# control_board.net
KiCad netlist of a schematic drawn in EAGLE
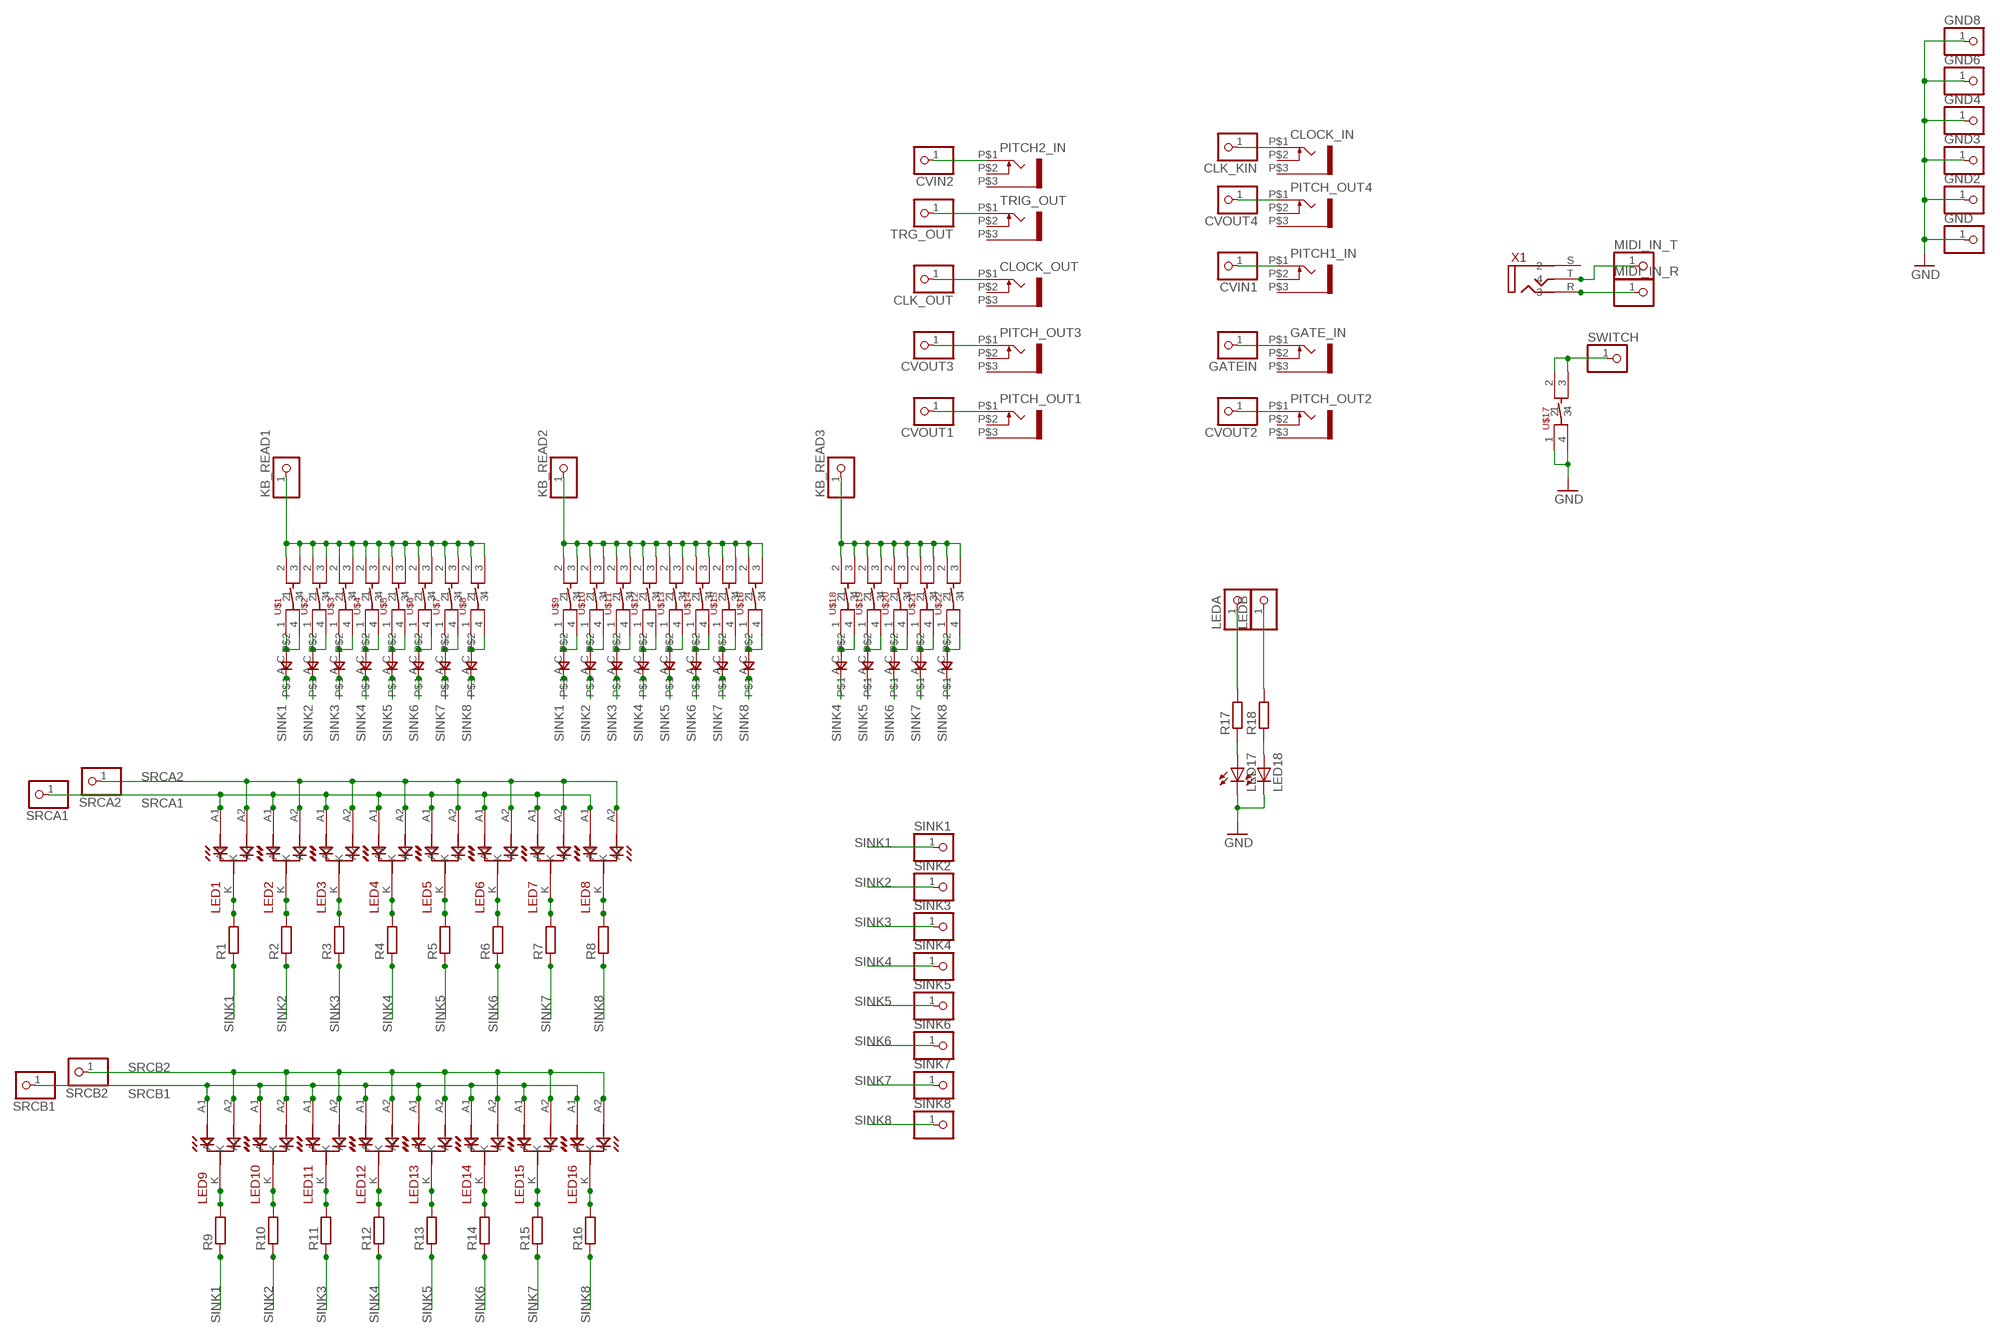
[diagram p0: schematic, sheet 1]

(export (version "E")
  (design (tool "Eeschema 10.0.6"))
  (components
    (comp (ref "CLK_KIN")
      (value "PINHD-1X1")
      (footprint "eagle-import:1X01")
      (libsource (lib "eagle-import") (part "PINHD-1X1"))
    )
    (comp (ref "CLK_OUT")
      (value "PINHD-1X1")
      (footprint "eagle-import:1X01")
      (libsource (lib "eagle-import") (part "PINHD-1X1"))
    )
    (comp (ref "CLOCK_IN")
      (value "WQP-PJ301M-12_JACK")
      (footprint "eagle-import:WQP-PJ301M-12_JACK")
      (libsource (lib "eagle-import") (part "WQP-PJ301M-12_JACK"))
    )
    (comp (ref "CLOCK_OUT")
      (value "WQP-PJ301M-12_JACK")
      (footprint "eagle-import:WQP-PJ301M-12_JACK")
      (libsource (lib "eagle-import") (part "WQP-PJ301M-12_JACK"))
    )
    (comp (ref "CVIN1")
      (value "PINHD-1X1")
      (footprint "eagle-import:1X01")
      (libsource (lib "eagle-import") (part "PINHD-1X1"))
    )
    (comp (ref "CVIN2")
      (value "PINHD-1X1")
      (footprint "eagle-import:1X01")
      (libsource (lib "eagle-import") (part "PINHD-1X1"))
    )
    (comp (ref "CVOUT1")
      (value "PINHD-1X1")
      (footprint "eagle-import:1X01")
      (libsource (lib "eagle-import") (part "PINHD-1X1"))
    )
    (comp (ref "CVOUT2")
      (value "PINHD-1X1")
      (footprint "eagle-import:1X01")
      (libsource (lib "eagle-import") (part "PINHD-1X1"))
    )
    (comp (ref "CVOUT3")
      (value "PINHD-1X1")
      (footprint "eagle-import:1X01")
      (libsource (lib "eagle-import") (part "PINHD-1X1"))
    )
    (comp (ref "CVOUT4")
      (value "PINHD-1X1")
      (footprint "eagle-import:1X01")
      (libsource (lib "eagle-import") (part "PINHD-1X1"))
    )
    (comp (ref "GATEIN")
      (value "PINHD-1X1")
      (footprint "eagle-import:1X01")
      (libsource (lib "eagle-import") (part "PINHD-1X1"))
    )
    (comp (ref "GATE_IN")
      (value "WQP-PJ301M-12_JACK")
      (footprint "eagle-import:WQP-PJ301M-12_JACK")
      (libsource (lib "eagle-import") (part "WQP-PJ301M-12_JACK"))
    )
    (comp (ref "GND")
      (value "PINHD-1X1")
      (footprint "eagle-import:1X01")
      (libsource (lib "eagle-import") (part "PINHD-1X1"))
    )
    (comp (ref "GND2")
      (value "PINHD-1X1")
      (footprint "eagle-import:1X01")
      (libsource (lib "eagle-import") (part "PINHD-1X1"))
    )
    (comp (ref "GND3")
      (value "PINHD-1X1")
      (footprint "eagle-import:1X01")
      (libsource (lib "eagle-import") (part "PINHD-1X1"))
    )
    (comp (ref "GND4")
      (value "PINHD-1X1")
      (footprint "eagle-import:1X01")
      (libsource (lib "eagle-import") (part "PINHD-1X1"))
    )
    (comp (ref "GND6")
      (value "PINHD-1X1")
      (footprint "eagle-import:1X01")
      (libsource (lib "eagle-import") (part "PINHD-1X1"))
    )
    (comp (ref "GND8")
      (value "PINHD-1X1")
      (footprint "eagle-import:1X01")
      (libsource (lib "eagle-import") (part "PINHD-1X1"))
    )
    (comp (ref "KB_READ1")
      (value "PINHD-1X1")
      (footprint "eagle-import:1X01")
      (libsource (lib "eagle-import") (part "PINHD-1X1"))
    )
    (comp (ref "KB_READ2")
      (value "PINHD-1X1")
      (footprint "eagle-import:1X01")
      (libsource (lib "eagle-import") (part "PINHD-1X1"))
    )
    (comp (ref "KB_READ3")
      (value "PINHD-1X1")
      (footprint "eagle-import:1X01")
      (libsource (lib "eagle-import") (part "PINHD-1X1"))
    )
    (comp (ref "LED1")
      (value "BICOL_LED_CC")
      (footprint "eagle-import:BICOL_LED_CC")
      (libsource (lib "eagle-import") (part "BICOL_LED_CC"))
    )
    (comp (ref "LED2")
      (value "BICOL_LED_CC")
      (footprint "eagle-import:BICOL_LED_CC")
      (libsource (lib "eagle-import") (part "BICOL_LED_CC"))
    )
    (comp (ref "LED3")
      (value "BICOL_LED_CC")
      (footprint "eagle-import:BICOL_LED_CC")
      (libsource (lib "eagle-import") (part "BICOL_LED_CC"))
    )
    (comp (ref "LED4")
      (value "BICOL_LED_CC")
      (footprint "eagle-import:BICOL_LED_CC")
      (libsource (lib "eagle-import") (part "BICOL_LED_CC"))
    )
    (comp (ref "LED5")
      (value "BICOL_LED_CC")
      (footprint "eagle-import:BICOL_LED_CC")
      (libsource (lib "eagle-import") (part "BICOL_LED_CC"))
    )
    (comp (ref "LED6")
      (value "BICOL_LED_CC")
      (footprint "eagle-import:BICOL_LED_CC")
      (libsource (lib "eagle-import") (part "BICOL_LED_CC"))
    )
    (comp (ref "LED7")
      (value "BICOL_LED_CC")
      (footprint "eagle-import:BICOL_LED_CC")
      (libsource (lib "eagle-import") (part "BICOL_LED_CC"))
    )
    (comp (ref "LED8")
      (value "BICOL_LED_CC")
      (footprint "eagle-import:BICOL_LED_CC")
      (libsource (lib "eagle-import") (part "BICOL_LED_CC"))
    )
    (comp (ref "LED9")
      (value "BICOL_LED_CC")
      (footprint "eagle-import:BICOL_LED_CC")
      (libsource (lib "eagle-import") (part "BICOL_LED_CC"))
    )
    (comp (ref "LED10")
      (value "BICOL_LED_CC")
      (footprint "eagle-import:BICOL_LED_CC")
      (libsource (lib "eagle-import") (part "BICOL_LED_CC"))
    )
    (comp (ref "LED11")
      (value "BICOL_LED_CC")
      (footprint "eagle-import:BICOL_LED_CC")
      (libsource (lib "eagle-import") (part "BICOL_LED_CC"))
    )
    (comp (ref "LED12")
      (value "BICOL_LED_CC")
      (footprint "eagle-import:BICOL_LED_CC")
      (libsource (lib "eagle-import") (part "BICOL_LED_CC"))
    )
    (comp (ref "LED13")
      (value "BICOL_LED_CC")
      (footprint "eagle-import:BICOL_LED_CC")
      (libsource (lib "eagle-import") (part "BICOL_LED_CC"))
    )
    (comp (ref "LED14")
      (value "BICOL_LED_CC")
      (footprint "eagle-import:BICOL_LED_CC")
      (libsource (lib "eagle-import") (part "BICOL_LED_CC"))
    )
    (comp (ref "LED15")
      (value "BICOL_LED_CC")
      (footprint "eagle-import:BICOL_LED_CC")
      (libsource (lib "eagle-import") (part "BICOL_LED_CC"))
    )
    (comp (ref "LED16")
      (value "BICOL_LED_CC")
      (footprint "eagle-import:BICOL_LED_CC")
      (libsource (lib "eagle-import") (part "BICOL_LED_CC"))
    )
    (comp (ref "LED17")
      (value "LED3MM")
      (footprint "eagle-import:LED3MM")
      (libsource (lib "eagle-import") (part "LED3MM"))
    )
    (comp (ref "LED18")
      (value "LED3MM")
      (footprint "eagle-import:LED3MM")
      (libsource (lib "eagle-import") (part "LED3MM"))
    )
    (comp (ref "LEDA")
      (value "PINHD-1X1")
      (footprint "eagle-import:1X01")
      (libsource (lib "eagle-import") (part "PINHD-1X1"))
    )
    (comp (ref "LEDB")
      (value "PINHD-1X1")
      (footprint "eagle-import:1X01")
      (libsource (lib "eagle-import") (part "PINHD-1X1"))
    )
    (comp (ref "MIDI_IN_R")
      (value "PINHD-1X1")
      (footprint "eagle-import:1X01")
      (libsource (lib "eagle-import") (part "PINHD-1X1"))
    )
    (comp (ref "MIDI_IN_T")
      (value "PINHD-1X1")
      (footprint "eagle-import:1X01")
      (libsource (lib "eagle-import") (part "PINHD-1X1"))
    )
    (comp (ref "PITCH1_IN")
      (value "WQP-PJ301M-12_JACK")
      (footprint "eagle-import:WQP-PJ301M-12_JACK")
      (libsource (lib "eagle-import") (part "WQP-PJ301M-12_JACK"))
    )
    (comp (ref "PITCH2_IN")
      (value "WQP-PJ301M-12_JACK")
      (footprint "eagle-import:WQP-PJ301M-12_JACK")
      (libsource (lib "eagle-import") (part "WQP-PJ301M-12_JACK"))
    )
    (comp (ref "PITCH_OUT1")
      (value "WQP-PJ301M-12_JACK")
      (footprint "eagle-import:WQP-PJ301M-12_JACK")
      (libsource (lib "eagle-import") (part "WQP-PJ301M-12_JACK"))
    )
    (comp (ref "PITCH_OUT2")
      (value "WQP-PJ301M-12_JACK")
      (footprint "eagle-import:WQP-PJ301M-12_JACK")
      (libsource (lib "eagle-import") (part "WQP-PJ301M-12_JACK"))
    )
    (comp (ref "PITCH_OUT3")
      (value "WQP-PJ301M-12_JACK")
      (footprint "eagle-import:WQP-PJ301M-12_JACK")
      (libsource (lib "eagle-import") (part "WQP-PJ301M-12_JACK"))
    )
    (comp (ref "PITCH_OUT4")
      (value "WQP-PJ301M-12_JACK")
      (footprint "eagle-import:WQP-PJ301M-12_JACK")
      (libsource (lib "eagle-import") (part "WQP-PJ301M-12_JACK"))
    )
    (comp (ref "R1")
      (value "R-EU_R0805")
      (footprint "eagle-import:R0805")
      (libsource (lib "eagle-import") (part "R-EU_R0805"))
    )
    (comp (ref "R2")
      (value "R-EU_R0805")
      (footprint "eagle-import:R0805")
      (libsource (lib "eagle-import") (part "R-EU_R0805"))
    )
    (comp (ref "R3")
      (value "R-EU_R0805")
      (footprint "eagle-import:R0805")
      (libsource (lib "eagle-import") (part "R-EU_R0805"))
    )
    (comp (ref "R4")
      (value "R-EU_R0805")
      (footprint "eagle-import:R0805")
      (libsource (lib "eagle-import") (part "R-EU_R0805"))
    )
    (comp (ref "R5")
      (value "R-EU_R0805")
      (footprint "eagle-import:R0805")
      (libsource (lib "eagle-import") (part "R-EU_R0805"))
    )
    (comp (ref "R6")
      (value "R-EU_R0805")
      (footprint "eagle-import:R0805")
      (libsource (lib "eagle-import") (part "R-EU_R0805"))
    )
    (comp (ref "R7")
      (value "R-EU_R0805")
      (footprint "eagle-import:R0805")
      (libsource (lib "eagle-import") (part "R-EU_R0805"))
    )
    (comp (ref "R8")
      (value "R-EU_R0805")
      (footprint "eagle-import:R0805")
      (libsource (lib "eagle-import") (part "R-EU_R0805"))
    )
    (comp (ref "R9")
      (value "R-EU_R0805")
      (footprint "eagle-import:R0805")
      (libsource (lib "eagle-import") (part "R-EU_R0805"))
    )
    (comp (ref "R10")
      (value "R-EU_R0805")
      (footprint "eagle-import:R0805")
      (libsource (lib "eagle-import") (part "R-EU_R0805"))
    )
    (comp (ref "R11")
      (value "R-EU_R0805")
      (footprint "eagle-import:R0805")
      (libsource (lib "eagle-import") (part "R-EU_R0805"))
    )
    (comp (ref "R12")
      (value "R-EU_R0805")
      (footprint "eagle-import:R0805")
      (libsource (lib "eagle-import") (part "R-EU_R0805"))
    )
    (comp (ref "R13")
      (value "R-EU_R0805")
      (footprint "eagle-import:R0805")
      (libsource (lib "eagle-import") (part "R-EU_R0805"))
    )
    (comp (ref "R14")
      (value "R-EU_R0805")
      (footprint "eagle-import:R0805")
      (libsource (lib "eagle-import") (part "R-EU_R0805"))
    )
    (comp (ref "R15")
      (value "R-EU_R0805")
      (footprint "eagle-import:R0805")
      (libsource (lib "eagle-import") (part "R-EU_R0805"))
    )
    (comp (ref "R16")
      (value "R-EU_R0805")
      (footprint "eagle-import:R0805")
      (libsource (lib "eagle-import") (part "R-EU_R0805"))
    )
    (comp (ref "R17")
      (value "R-EU_R0805")
      (footprint "eagle-import:R0805")
      (libsource (lib "eagle-import") (part "R-EU_R0805"))
    )
    (comp (ref "R18")
      (value "R-EU_R0805")
      (footprint "eagle-import:R0805")
      (libsource (lib "eagle-import") (part "R-EU_R0805"))
    )
    (comp (ref "SINK1")
      (value "PINHD-1X1")
      (footprint "eagle-import:1X01")
      (libsource (lib "eagle-import") (part "PINHD-1X1"))
    )
    (comp (ref "SINK2")
      (value "PINHD-1X1")
      (footprint "eagle-import:1X01")
      (libsource (lib "eagle-import") (part "PINHD-1X1"))
    )
    (comp (ref "SINK3")
      (value "PINHD-1X1")
      (footprint "eagle-import:1X01")
      (libsource (lib "eagle-import") (part "PINHD-1X1"))
    )
    (comp (ref "SINK4")
      (value "PINHD-1X1")
      (footprint "eagle-import:1X01")
      (libsource (lib "eagle-import") (part "PINHD-1X1"))
    )
    (comp (ref "SINK5")
      (value "PINHD-1X1")
      (footprint "eagle-import:1X01")
      (libsource (lib "eagle-import") (part "PINHD-1X1"))
    )
    (comp (ref "SINK6")
      (value "PINHD-1X1")
      (footprint "eagle-import:1X01")
      (libsource (lib "eagle-import") (part "PINHD-1X1"))
    )
    (comp (ref "SINK7")
      (value "PINHD-1X1")
      (footprint "eagle-import:1X01")
      (libsource (lib "eagle-import") (part "PINHD-1X1"))
    )
    (comp (ref "SINK8")
      (value "PINHD-1X1")
      (footprint "eagle-import:1X01")
      (libsource (lib "eagle-import") (part "PINHD-1X1"))
    )
    (comp (ref "SRCA1")
      (value "PINHD-1X1")
      (footprint "eagle-import:1X01")
      (libsource (lib "eagle-import") (part "PINHD-1X1"))
    )
    (comp (ref "SRCA2")
      (value "PINHD-1X1")
      (footprint "eagle-import:1X01")
      (libsource (lib "eagle-import") (part "PINHD-1X1"))
    )
    (comp (ref "SRCB1")
      (value "PINHD-1X1")
      (footprint "eagle-import:1X01")
      (libsource (lib "eagle-import") (part "PINHD-1X1"))
    )
    (comp (ref "SRCB2")
      (value "PINHD-1X1")
      (footprint "eagle-import:1X01")
      (libsource (lib "eagle-import") (part "PINHD-1X1"))
    )
    (comp (ref "SWITCH")
      (value "PINHD-1X1")
      (footprint "eagle-import:1X01")
      (libsource (lib "eagle-import") (part "PINHD-1X1"))
    )
    (comp (ref "TRG_OUT")
      (value "PINHD-1X1")
      (footprint "eagle-import:1X01")
      (libsource (lib "eagle-import") (part "PINHD-1X1"))
    )
    (comp (ref "TRIG_OUT")
      (value "WQP-PJ301M-12_JACK")
      (footprint "eagle-import:WQP-PJ301M-12_JACK")
      (libsource (lib "eagle-import") (part "WQP-PJ301M-12_JACK"))
    )
    (comp (ref "U$1")
      (value "6MM_TACT")
      (footprint "eagle-import:6MMTACT")
      (libsource (lib "eagle-import") (part "6MM_TACT"))
    )
    (comp (ref "U$2")
      (value "6MM_TACT")
      (footprint "eagle-import:6MMTACT")
      (libsource (lib "eagle-import") (part "6MM_TACT"))
    )
    (comp (ref "U$3")
      (value "6MM_TACT")
      (footprint "eagle-import:6MMTACT")
      (libsource (lib "eagle-import") (part "6MM_TACT"))
    )
    (comp (ref "U$4")
      (value "6MM_TACT")
      (footprint "eagle-import:6MMTACT")
      (libsource (lib "eagle-import") (part "6MM_TACT"))
    )
    (comp (ref "U$5")
      (value "6MM_TACT")
      (footprint "eagle-import:6MMTACT")
      (libsource (lib "eagle-import") (part "6MM_TACT"))
    )
    (comp (ref "U$6")
      (value "6MM_TACT")
      (footprint "eagle-import:6MMTACT")
      (libsource (lib "eagle-import") (part "6MM_TACT"))
    )
    (comp (ref "U$7")
      (value "6MM_TACT")
      (footprint "eagle-import:6MMTACT")
      (libsource (lib "eagle-import") (part "6MM_TACT"))
    )
    (comp (ref "U$8")
      (value "6MM_TACT")
      (footprint "eagle-import:6MMTACT")
      (libsource (lib "eagle-import") (part "6MM_TACT"))
    )
    (comp (ref "U$9")
      (value "6MM_TACT")
      (footprint "eagle-import:6MMTACT")
      (libsource (lib "eagle-import") (part "6MM_TACT"))
    )
    (comp (ref "U$10")
      (value "6MM_TACT")
      (footprint "eagle-import:6MMTACT")
      (libsource (lib "eagle-import") (part "6MM_TACT"))
    )
    (comp (ref "U$11")
      (value "6MM_TACT")
      (footprint "eagle-import:6MMTACT")
      (libsource (lib "eagle-import") (part "6MM_TACT"))
    )
    (comp (ref "U$12")
      (value "6MM_TACT")
      (footprint "eagle-import:6MMTACT")
      (libsource (lib "eagle-import") (part "6MM_TACT"))
    )
    (comp (ref "U$13")
      (value "6MM_TACT")
      (footprint "eagle-import:6MMTACT")
      (libsource (lib "eagle-import") (part "6MM_TACT"))
    )
    (comp (ref "U$14")
      (value "6MM_TACT")
      (footprint "eagle-import:6MMTACT")
      (libsource (lib "eagle-import") (part "6MM_TACT"))
    )
    (comp (ref "U$15")
      (value "6MM_TACT")
      (footprint "eagle-import:6MMTACT")
      (libsource (lib "eagle-import") (part "6MM_TACT"))
    )
    (comp (ref "U$16")
      (value "6MM_TACT")
      (footprint "eagle-import:6MMTACT")
      (libsource (lib "eagle-import") (part "6MM_TACT"))
    )
    (comp (ref "U$17")
      (value "6MM_TACT")
      (footprint "eagle-import:6MMTACT")
      (libsource (lib "eagle-import") (part "6MM_TACT"))
    )
    (comp (ref "U$18")
      (value "6MM_TACT")
      (footprint "eagle-import:6MMTACT")
      (libsource (lib "eagle-import") (part "6MM_TACT"))
    )
    (comp (ref "U$19")
      (value "6MM_TACT")
      (footprint "eagle-import:6MMTACT")
      (libsource (lib "eagle-import") (part "6MM_TACT"))
    )
    (comp (ref "U$20")
      (value "6MM_TACT")
      (footprint "eagle-import:6MMTACT")
      (libsource (lib "eagle-import") (part "6MM_TACT"))
    )
    (comp (ref "U$21")
      (value "6MM_TACT")
      (footprint "eagle-import:6MMTACT")
      (libsource (lib "eagle-import") (part "6MM_TACT"))
    )
    (comp (ref "U$22")
      (value "6MM_TACT")
      (footprint "eagle-import:6MMTACT")
      (libsource (lib "eagle-import") (part "6MM_TACT"))
    )
    (comp (ref "U$23")
      (value "0805DIODE")
      (footprint "eagle-import:0805DIODE")
      (libsource (lib "eagle-import") (part "0805DIODE"))
    )
    (comp (ref "U$24")
      (value "0805DIODE")
      (footprint "eagle-import:0805DIODE")
      (libsource (lib "eagle-import") (part "0805DIODE"))
    )
    (comp (ref "U$25")
      (value "0805DIODE")
      (footprint "eagle-import:0805DIODE")
      (libsource (lib "eagle-import") (part "0805DIODE"))
    )
    (comp (ref "U$26")
      (value "0805DIODE")
      (footprint "eagle-import:0805DIODE")
      (libsource (lib "eagle-import") (part "0805DIODE"))
    )
    (comp (ref "U$27")
      (value "0805DIODE")
      (footprint "eagle-import:0805DIODE")
      (libsource (lib "eagle-import") (part "0805DIODE"))
    )
    (comp (ref "U$28")
      (value "0805DIODE")
      (footprint "eagle-import:0805DIODE")
      (libsource (lib "eagle-import") (part "0805DIODE"))
    )
    (comp (ref "U$29")
      (value "0805DIODE")
      (footprint "eagle-import:0805DIODE")
      (libsource (lib "eagle-import") (part "0805DIODE"))
    )
    (comp (ref "U$30")
      (value "0805DIODE")
      (footprint "eagle-import:0805DIODE")
      (libsource (lib "eagle-import") (part "0805DIODE"))
    )
    (comp (ref "U$31")
      (value "0805DIODE")
      (footprint "eagle-import:0805DIODE")
      (libsource (lib "eagle-import") (part "0805DIODE"))
    )
    (comp (ref "U$32")
      (value "0805DIODE")
      (footprint "eagle-import:0805DIODE")
      (libsource (lib "eagle-import") (part "0805DIODE"))
    )
    (comp (ref "U$33")
      (value "0805DIODE")
      (footprint "eagle-import:0805DIODE")
      (libsource (lib "eagle-import") (part "0805DIODE"))
    )
    (comp (ref "U$34")
      (value "0805DIODE")
      (footprint "eagle-import:0805DIODE")
      (libsource (lib "eagle-import") (part "0805DIODE"))
    )
    (comp (ref "U$35")
      (value "0805DIODE")
      (footprint "eagle-import:0805DIODE")
      (libsource (lib "eagle-import") (part "0805DIODE"))
    )
    (comp (ref "U$36")
      (value "0805DIODE")
      (footprint "eagle-import:0805DIODE")
      (libsource (lib "eagle-import") (part "0805DIODE"))
    )
    (comp (ref "U$37")
      (value "0805DIODE")
      (footprint "eagle-import:0805DIODE")
      (libsource (lib "eagle-import") (part "0805DIODE"))
    )
    (comp (ref "U$38")
      (value "0805DIODE")
      (footprint "eagle-import:0805DIODE")
      (libsource (lib "eagle-import") (part "0805DIODE"))
    )
    (comp (ref "U$39")
      (value "0805DIODE")
      (footprint "eagle-import:0805DIODE")
      (libsource (lib "eagle-import") (part "0805DIODE"))
    )
    (comp (ref "U$40")
      (value "0805DIODE")
      (footprint "eagle-import:0805DIODE")
      (libsource (lib "eagle-import") (part "0805DIODE"))
    )
    (comp (ref "U$41")
      (value "0805DIODE")
      (footprint "eagle-import:0805DIODE")
      (libsource (lib "eagle-import") (part "0805DIODE"))
    )
    (comp (ref "U$42")
      (value "0805DIODE")
      (footprint "eagle-import:0805DIODE")
      (libsource (lib "eagle-import") (part "0805DIODE"))
    )
    (comp (ref "U$43")
      (value "0805DIODE")
      (footprint "eagle-import:0805DIODE")
      (libsource (lib "eagle-import") (part "0805DIODE"))
    )
    (comp (ref "X1")
      (value "VERTICAL_3_5MM_SOCKETTHONK")
      (footprint "eagle-import:PJ301CM")
      (libsource (lib "eagle-import") (part "VERTICAL_3_5MM_SOCKETTHONK"))
    )
  )
  (nets
    (net (code "1") (name "/SINK1") (class "Default")
      (node (ref "R1") (pin "1") (pinfunction "1_1") (pintype "passive"))
      (node (ref "R9") (pin "1") (pinfunction "1_1") (pintype "passive"))
      (node (ref "SINK1") (pin "1") (pinfunction "1_1") (pintype "passive"))
      (node (ref "U$23") (pin "A") (pinfunction "P$2_A") (pintype "bidirectional"))
      (node (ref "U$31") (pin "A") (pinfunction "P$2_A") (pintype "bidirectional"))
    )
    (net (code "2") (name "/SINK2") (class "Default")
      (node (ref "R10") (pin "1") (pinfunction "1_1") (pintype "passive"))
      (node (ref "R2") (pin "1") (pinfunction "1_1") (pintype "passive"))
      (node (ref "SINK2") (pin "1") (pinfunction "1_1") (pintype "passive"))
      (node (ref "U$24") (pin "A") (pinfunction "P$2_A") (pintype "bidirectional"))
      (node (ref "U$32") (pin "A") (pinfunction "P$2_A") (pintype "bidirectional"))
    )
    (net (code "3") (name "/SINK3") (class "Default")
      (node (ref "R11") (pin "1") (pinfunction "1_1") (pintype "passive"))
      (node (ref "R3") (pin "1") (pinfunction "1_1") (pintype "passive"))
      (node (ref "SINK3") (pin "1") (pinfunction "1_1") (pintype "passive"))
      (node (ref "U$25") (pin "A") (pinfunction "P$2_A") (pintype "bidirectional"))
      (node (ref "U$33") (pin "A") (pinfunction "P$2_A") (pintype "bidirectional"))
    )
    (net (code "4") (name "/SINK4") (class "Default")
      (node (ref "R12") (pin "1") (pinfunction "1_1") (pintype "passive"))
      (node (ref "R4") (pin "1") (pinfunction "1_1") (pintype "passive"))
      (node (ref "SINK4") (pin "1") (pinfunction "1_1") (pintype "passive"))
      (node (ref "U$26") (pin "A") (pinfunction "P$2_A") (pintype "bidirectional"))
      (node (ref "U$34") (pin "A") (pinfunction "P$2_A") (pintype "bidirectional"))
      (node (ref "U$39") (pin "A") (pinfunction "P$2_A") (pintype "bidirectional"))
    )
    (net (code "5") (name "/SINK5") (class "Default")
      (node (ref "R13") (pin "1") (pinfunction "1_1") (pintype "passive"))
      (node (ref "R5") (pin "1") (pinfunction "1_1") (pintype "passive"))
      (node (ref "SINK5") (pin "1") (pinfunction "1_1") (pintype "passive"))
      (node (ref "U$27") (pin "A") (pinfunction "P$2_A") (pintype "bidirectional"))
      (node (ref "U$35") (pin "A") (pinfunction "P$2_A") (pintype "bidirectional"))
      (node (ref "U$40") (pin "A") (pinfunction "P$2_A") (pintype "bidirectional"))
    )
    (net (code "6") (name "/SINK6") (class "Default")
      (node (ref "R14") (pin "1") (pinfunction "1_1") (pintype "passive"))
      (node (ref "R6") (pin "1") (pinfunction "1_1") (pintype "passive"))
      (node (ref "SINK6") (pin "1") (pinfunction "1_1") (pintype "passive"))
      (node (ref "U$28") (pin "A") (pinfunction "P$2_A") (pintype "bidirectional"))
      (node (ref "U$36") (pin "A") (pinfunction "P$2_A") (pintype "bidirectional"))
      (node (ref "U$41") (pin "A") (pinfunction "P$2_A") (pintype "bidirectional"))
    )
    (net (code "7") (name "/SINK7") (class "Default")
      (node (ref "R15") (pin "1") (pinfunction "1_1") (pintype "passive"))
      (node (ref "R7") (pin "1") (pinfunction "1_1") (pintype "passive"))
      (node (ref "SINK7") (pin "1") (pinfunction "1_1") (pintype "passive"))
      (node (ref "U$29") (pin "A") (pinfunction "P$2_A") (pintype "bidirectional"))
      (node (ref "U$37") (pin "A") (pinfunction "P$2_A") (pintype "bidirectional"))
      (node (ref "U$42") (pin "A") (pinfunction "P$2_A") (pintype "bidirectional"))
    )
    (net (code "8") (name "/SINK8") (class "Default")
      (node (ref "R16") (pin "1") (pinfunction "1_1") (pintype "passive"))
      (node (ref "R8") (pin "1") (pinfunction "1_1") (pintype "passive"))
      (node (ref "SINK8") (pin "1") (pinfunction "1_1") (pintype "passive"))
      (node (ref "U$30") (pin "A") (pinfunction "P$2_A") (pintype "bidirectional"))
      (node (ref "U$38") (pin "A") (pinfunction "P$2_A") (pintype "bidirectional"))
      (node (ref "U$43") (pin "A") (pinfunction "P$2_A") (pintype "bidirectional"))
    )
    (net (code "9") (name "/SRCA1") (class "Default")
      (node (ref "LED1") (pin "A1") (pinfunction "A1_A1") (pintype "bidirectional"))
      (node (ref "LED2") (pin "A1") (pinfunction "A1_A1") (pintype "bidirectional"))
      (node (ref "LED3") (pin "A1") (pinfunction "A1_A1") (pintype "bidirectional"))
      (node (ref "LED4") (pin "A1") (pinfunction "A1_A1") (pintype "bidirectional"))
      (node (ref "LED5") (pin "A1") (pinfunction "A1_A1") (pintype "bidirectional"))
      (node (ref "LED6") (pin "A1") (pinfunction "A1_A1") (pintype "bidirectional"))
      (node (ref "LED7") (pin "A1") (pinfunction "A1_A1") (pintype "bidirectional"))
      (node (ref "LED8") (pin "A1") (pinfunction "A1_A1") (pintype "bidirectional"))
      (node (ref "SRCA1") (pin "1") (pinfunction "1_1") (pintype "passive"))
    )
    (net (code "10") (name "/SRCA2") (class "Default")
      (node (ref "LED1") (pin "A2") (pinfunction "A2_A2") (pintype "bidirectional"))
      (node (ref "LED2") (pin "A2") (pinfunction "A2_A2") (pintype "bidirectional"))
      (node (ref "LED3") (pin "A2") (pinfunction "A2_A2") (pintype "bidirectional"))
      (node (ref "LED4") (pin "A2") (pinfunction "A2_A2") (pintype "bidirectional"))
      (node (ref "LED5") (pin "A2") (pinfunction "A2_A2") (pintype "bidirectional"))
      (node (ref "LED6") (pin "A2") (pinfunction "A2_A2") (pintype "bidirectional"))
      (node (ref "LED7") (pin "A2") (pinfunction "A2_A2") (pintype "bidirectional"))
      (node (ref "LED8") (pin "A2") (pinfunction "A2_A2") (pintype "bidirectional"))
      (node (ref "SRCA2") (pin "1") (pinfunction "1_1") (pintype "passive"))
    )
    (net (code "11") (name "/SRCB1") (class "Default")
      (node (ref "LED10") (pin "A1") (pinfunction "A1_A1") (pintype "bidirectional"))
      (node (ref "LED11") (pin "A1") (pinfunction "A1_A1") (pintype "bidirectional"))
      (node (ref "LED12") (pin "A1") (pinfunction "A1_A1") (pintype "bidirectional"))
      (node (ref "LED13") (pin "A1") (pinfunction "A1_A1") (pintype "bidirectional"))
      (node (ref "LED14") (pin "A1") (pinfunction "A1_A1") (pintype "bidirectional"))
      (node (ref "LED15") (pin "A1") (pinfunction "A1_A1") (pintype "bidirectional"))
      (node (ref "LED16") (pin "A1") (pinfunction "A1_A1") (pintype "bidirectional"))
      (node (ref "LED9") (pin "A1") (pinfunction "A1_A1") (pintype "bidirectional"))
      (node (ref "SRCB1") (pin "1") (pinfunction "1_1") (pintype "passive"))
    )
    (net (code "12") (name "/SRCB2") (class "Default")
      (node (ref "LED10") (pin "A2") (pinfunction "A2_A2") (pintype "bidirectional"))
      (node (ref "LED11") (pin "A2") (pinfunction "A2_A2") (pintype "bidirectional"))
      (node (ref "LED12") (pin "A2") (pinfunction "A2_A2") (pintype "bidirectional"))
      (node (ref "LED13") (pin "A2") (pinfunction "A2_A2") (pintype "bidirectional"))
      (node (ref "LED14") (pin "A2") (pinfunction "A2_A2") (pintype "bidirectional"))
      (node (ref "LED15") (pin "A2") (pinfunction "A2_A2") (pintype "bidirectional"))
      (node (ref "LED16") (pin "A2") (pinfunction "A2_A2") (pintype "bidirectional"))
      (node (ref "LED9") (pin "A2") (pinfunction "A2_A2") (pintype "bidirectional"))
      (node (ref "SRCB2") (pin "1") (pinfunction "1_1") (pintype "passive"))
    )
    (net (code "13") (name "GND") (class "Default")
      (node (ref "GND") (pin "1") (pinfunction "1_1") (pintype "passive"))
      (node (ref "GND2") (pin "1") (pinfunction "1_1") (pintype "passive"))
      (node (ref "GND3") (pin "1") (pinfunction "1_1") (pintype "passive"))
      (node (ref "GND4") (pin "1") (pinfunction "1_1") (pintype "passive"))
      (node (ref "GND6") (pin "1") (pinfunction "1_1") (pintype "passive"))
      (node (ref "GND8") (pin "1") (pinfunction "1_1") (pintype "passive"))
      (node (ref "LED17") (pin "K") (pinfunction "C_K") (pintype "passive"))
      (node (ref "LED18") (pin "K") (pinfunction "C_K") (pintype "passive"))
      (node (ref "U$17") (pin "1") (pinfunction "1_1") (pintype "bidirectional"))
      (node (ref "U$17") (pin "4") (pinfunction "4_4") (pintype "bidirectional"))
    )
    (net (code "14") (name "Net-(CLOCK_IN-2)") (class "Default")
      (node (ref "CLK_KIN") (pin "1") (pinfunction "1_1") (pintype "passive"))
      (node (ref "CLOCK_IN") (pin "P$1") (pinfunction "2_P$1") (pintype "passive"))
    )
    (net (code "15") (name "Net-(CLOCK_OUT-2)") (class "Default")
      (node (ref "CLK_OUT") (pin "1") (pinfunction "1_1") (pintype "passive"))
      (node (ref "CLOCK_OUT") (pin "P$1") (pinfunction "2_P$1") (pintype "passive"))
    )
    (net (code "16") (name "Net-(GATE_IN-2)") (class "Default")
      (node (ref "GATEIN") (pin "1") (pinfunction "1_1") (pintype "passive"))
      (node (ref "GATE_IN") (pin "P$1") (pinfunction "2_P$1") (pintype "passive"))
    )
    (net (code "17") (name "Net-(KB_READ1-Pad1)") (class "Default")
      (node (ref "KB_READ1") (pin "1") (pinfunction "1_1") (pintype "passive"))
      (node (ref "U$1") (pin "2") (pinfunction "2_2") (pintype "bidirectional"))
      (node (ref "U$1") (pin "3") (pinfunction "3_3") (pintype "bidirectional"))
      (node (ref "U$2") (pin "2") (pinfunction "2_2") (pintype "bidirectional"))
      (node (ref "U$2") (pin "3") (pinfunction "3_3") (pintype "bidirectional"))
      (node (ref "U$3") (pin "2") (pinfunction "2_2") (pintype "bidirectional"))
      (node (ref "U$3") (pin "3") (pinfunction "3_3") (pintype "bidirectional"))
      (node (ref "U$4") (pin "2") (pinfunction "2_2") (pintype "bidirectional"))
      (node (ref "U$4") (pin "3") (pinfunction "3_3") (pintype "bidirectional"))
      (node (ref "U$5") (pin "2") (pinfunction "2_2") (pintype "bidirectional"))
      (node (ref "U$5") (pin "3") (pinfunction "3_3") (pintype "bidirectional"))
      (node (ref "U$6") (pin "2") (pinfunction "2_2") (pintype "bidirectional"))
      (node (ref "U$6") (pin "3") (pinfunction "3_3") (pintype "bidirectional"))
      (node (ref "U$7") (pin "2") (pinfunction "2_2") (pintype "bidirectional"))
      (node (ref "U$7") (pin "3") (pinfunction "3_3") (pintype "bidirectional"))
      (node (ref "U$8") (pin "2") (pinfunction "2_2") (pintype "bidirectional"))
      (node (ref "U$8") (pin "3") (pinfunction "3_3") (pintype "bidirectional"))
    )
    (net (code "18") (name "Net-(KB_READ2-Pad1)") (class "Default")
      (node (ref "KB_READ2") (pin "1") (pinfunction "1_1") (pintype "passive"))
      (node (ref "U$10") (pin "2") (pinfunction "2_2") (pintype "bidirectional"))
      (node (ref "U$10") (pin "3") (pinfunction "3_3") (pintype "bidirectional"))
      (node (ref "U$11") (pin "2") (pinfunction "2_2") (pintype "bidirectional"))
      (node (ref "U$11") (pin "3") (pinfunction "3_3") (pintype "bidirectional"))
      (node (ref "U$12") (pin "2") (pinfunction "2_2") (pintype "bidirectional"))
      (node (ref "U$12") (pin "3") (pinfunction "3_3") (pintype "bidirectional"))
      (node (ref "U$13") (pin "2") (pinfunction "2_2") (pintype "bidirectional"))
      (node (ref "U$13") (pin "3") (pinfunction "3_3") (pintype "bidirectional"))
      (node (ref "U$14") (pin "2") (pinfunction "2_2") (pintype "bidirectional"))
      (node (ref "U$14") (pin "3") (pinfunction "3_3") (pintype "bidirectional"))
      (node (ref "U$15") (pin "2") (pinfunction "2_2") (pintype "bidirectional"))
      (node (ref "U$15") (pin "3") (pinfunction "3_3") (pintype "bidirectional"))
      (node (ref "U$16") (pin "2") (pinfunction "2_2") (pintype "bidirectional"))
      (node (ref "U$16") (pin "3") (pinfunction "3_3") (pintype "bidirectional"))
      (node (ref "U$9") (pin "2") (pinfunction "2_2") (pintype "bidirectional"))
      (node (ref "U$9") (pin "3") (pinfunction "3_3") (pintype "bidirectional"))
    )
    (net (code "19") (name "Net-(KB_READ3-Pad1)") (class "Default")
      (node (ref "KB_READ3") (pin "1") (pinfunction "1_1") (pintype "passive"))
      (node (ref "U$18") (pin "2") (pinfunction "2_2") (pintype "bidirectional"))
      (node (ref "U$18") (pin "3") (pinfunction "3_3") (pintype "bidirectional"))
      (node (ref "U$19") (pin "2") (pinfunction "2_2") (pintype "bidirectional"))
      (node (ref "U$19") (pin "3") (pinfunction "3_3") (pintype "bidirectional"))
      (node (ref "U$20") (pin "2") (pinfunction "2_2") (pintype "bidirectional"))
      (node (ref "U$20") (pin "3") (pinfunction "3_3") (pintype "bidirectional"))
      (node (ref "U$21") (pin "2") (pinfunction "2_2") (pintype "bidirectional"))
      (node (ref "U$21") (pin "3") (pinfunction "3_3") (pintype "bidirectional"))
      (node (ref "U$22") (pin "2") (pinfunction "2_2") (pintype "bidirectional"))
      (node (ref "U$22") (pin "3") (pinfunction "3_3") (pintype "bidirectional"))
    )
    (net (code "20") (name "Net-(LED1-PadK)") (class "Default")
      (node (ref "LED1") (pin "K") (pinfunction "K_K") (pintype "bidirectional"))
      (node (ref "R1") (pin "2") (pinfunction "2_2") (pintype "passive"))
    )
    (net (code "21") (name "Net-(LED2-PadK)") (class "Default")
      (node (ref "LED2") (pin "K") (pinfunction "K_K") (pintype "bidirectional"))
      (node (ref "R2") (pin "2") (pinfunction "2_2") (pintype "passive"))
    )
    (net (code "22") (name "Net-(LED3-PadK)") (class "Default")
      (node (ref "LED3") (pin "K") (pinfunction "K_K") (pintype "bidirectional"))
      (node (ref "R3") (pin "2") (pinfunction "2_2") (pintype "passive"))
    )
    (net (code "23") (name "Net-(LED4-PadK)") (class "Default")
      (node (ref "LED4") (pin "K") (pinfunction "K_K") (pintype "bidirectional"))
      (node (ref "R4") (pin "2") (pinfunction "2_2") (pintype "passive"))
    )
    (net (code "24") (name "Net-(LED5-PadK)") (class "Default")
      (node (ref "LED5") (pin "K") (pinfunction "K_K") (pintype "bidirectional"))
      (node (ref "R5") (pin "2") (pinfunction "2_2") (pintype "passive"))
    )
    (net (code "25") (name "Net-(LED6-PadK)") (class "Default")
      (node (ref "LED6") (pin "K") (pinfunction "K_K") (pintype "bidirectional"))
      (node (ref "R6") (pin "2") (pinfunction "2_2") (pintype "passive"))
    )
    (net (code "26") (name "Net-(LED7-PadK)") (class "Default")
      (node (ref "LED7") (pin "K") (pinfunction "K_K") (pintype "bidirectional"))
      (node (ref "R7") (pin "2") (pinfunction "2_2") (pintype "passive"))
    )
    (net (code "27") (name "Net-(LED8-PadK)") (class "Default")
      (node (ref "LED8") (pin "K") (pinfunction "K_K") (pintype "bidirectional"))
      (node (ref "R8") (pin "2") (pinfunction "2_2") (pintype "passive"))
    )
    (net (code "28") (name "Net-(LED9-PadK)") (class "Default")
      (node (ref "LED9") (pin "K") (pinfunction "K_K") (pintype "bidirectional"))
      (node (ref "R9") (pin "2") (pinfunction "2_2") (pintype "passive"))
    )
    (net (code "29") (name "Net-(LED10-PadK)") (class "Default")
      (node (ref "LED10") (pin "K") (pinfunction "K_K") (pintype "bidirectional"))
      (node (ref "R10") (pin "2") (pinfunction "2_2") (pintype "passive"))
    )
    (net (code "30") (name "Net-(LED11-PadK)") (class "Default")
      (node (ref "LED11") (pin "K") (pinfunction "K_K") (pintype "bidirectional"))
      (node (ref "R11") (pin "2") (pinfunction "2_2") (pintype "passive"))
    )
    (net (code "31") (name "Net-(LED12-PadK)") (class "Default")
      (node (ref "LED12") (pin "K") (pinfunction "K_K") (pintype "bidirectional"))
      (node (ref "R12") (pin "2") (pinfunction "2_2") (pintype "passive"))
    )
    (net (code "32") (name "Net-(LED13-PadK)") (class "Default")
      (node (ref "LED13") (pin "K") (pinfunction "K_K") (pintype "bidirectional"))
      (node (ref "R13") (pin "2") (pinfunction "2_2") (pintype "passive"))
    )
    (net (code "33") (name "Net-(LED14-PadK)") (class "Default")
      (node (ref "LED14") (pin "K") (pinfunction "K_K") (pintype "bidirectional"))
      (node (ref "R14") (pin "2") (pinfunction "2_2") (pintype "passive"))
    )
    (net (code "34") (name "Net-(LED15-PadK)") (class "Default")
      (node (ref "LED15") (pin "K") (pinfunction "K_K") (pintype "bidirectional"))
      (node (ref "R15") (pin "2") (pinfunction "2_2") (pintype "passive"))
    )
    (net (code "35") (name "Net-(LED16-PadK)") (class "Default")
      (node (ref "LED16") (pin "K") (pinfunction "K_K") (pintype "bidirectional"))
      (node (ref "R16") (pin "2") (pinfunction "2_2") (pintype "passive"))
    )
    (net (code "36") (name "Net-(LED17-PadA)") (class "Default")
      (node (ref "LED17") (pin "A") (pinfunction "A_A") (pintype "passive"))
      (node (ref "R17") (pin "1") (pinfunction "1_1") (pintype "passive"))
    )
    (net (code "37") (name "Net-(LED18-PadA)") (class "Default")
      (node (ref "LED18") (pin "A") (pinfunction "A_A") (pintype "passive"))
      (node (ref "R18") (pin "1") (pinfunction "1_1") (pintype "passive"))
    )
    (net (code "38") (name "Net-(LEDA-Pad1)") (class "Default")
      (node (ref "LEDA") (pin "1") (pinfunction "1_1") (pintype "passive"))
      (node (ref "R17") (pin "2") (pinfunction "2_2") (pintype "passive"))
    )
    (net (code "39") (name "Net-(LEDB-Pad1)") (class "Default")
      (node (ref "LEDB") (pin "1") (pinfunction "1_1") (pintype "passive"))
      (node (ref "R18") (pin "2") (pinfunction "2_2") (pintype "passive"))
    )
    (net (code "40") (name "Net-(PITCH1_IN-2)") (class "Default")
      (node (ref "CVIN1") (pin "1") (pinfunction "1_1") (pintype "passive"))
      (node (ref "PITCH1_IN") (pin "P$1") (pinfunction "2_P$1") (pintype "passive"))
    )
    (net (code "41") (name "Net-(PITCH2_IN-2)") (class "Default")
      (node (ref "CVIN2") (pin "1") (pinfunction "1_1") (pintype "passive"))
      (node (ref "PITCH2_IN") (pin "P$1") (pinfunction "2_P$1") (pintype "passive"))
    )
    (net (code "42") (name "Net-(PITCH_OUT1-2)") (class "Default")
      (node (ref "CVOUT1") (pin "1") (pinfunction "1_1") (pintype "passive"))
      (node (ref "PITCH_OUT1") (pin "P$1") (pinfunction "2_P$1") (pintype "passive"))
    )
    (net (code "43") (name "Net-(PITCH_OUT2-2)") (class "Default")
      (node (ref "CVOUT2") (pin "1") (pinfunction "1_1") (pintype "passive"))
      (node (ref "PITCH_OUT2") (pin "P$1") (pinfunction "2_P$1") (pintype "passive"))
    )
    (net (code "44") (name "Net-(PITCH_OUT3-2)") (class "Default")
      (node (ref "CVOUT3") (pin "1") (pinfunction "1_1") (pintype "passive"))
      (node (ref "PITCH_OUT3") (pin "P$1") (pinfunction "2_P$1") (pintype "passive"))
    )
    (net (code "45") (name "Net-(PITCH_OUT4-2)") (class "Default")
      (node (ref "CVOUT4") (pin "1") (pinfunction "1_1") (pintype "passive"))
      (node (ref "PITCH_OUT4") (pin "P$1") (pinfunction "2_P$1") (pintype "passive"))
    )
    (net (code "46") (name "Net-(SWITCH-Pad1)") (class "Default")
      (node (ref "SWITCH") (pin "1") (pinfunction "1_1") (pintype "passive"))
      (node (ref "U$17") (pin "2") (pinfunction "2_2") (pintype "bidirectional"))
      (node (ref "U$17") (pin "3") (pinfunction "3_3") (pintype "bidirectional"))
    )
    (net (code "47") (name "Net-(TRIG_OUT-2)") (class "Default")
      (node (ref "TRG_OUT") (pin "1") (pinfunction "1_1") (pintype "passive"))
      (node (ref "TRIG_OUT") (pin "P$1") (pinfunction "2_P$1") (pintype "passive"))
    )
    (net (code "48") (name "Net-(U$23-P$1)") (class "Default")
      (node (ref "U$1") (pin "1") (pinfunction "1_1") (pintype "bidirectional"))
      (node (ref "U$1") (pin "4") (pinfunction "4_4") (pintype "bidirectional"))
      (node (ref "U$23") (pin "C") (pinfunction "P$1_C") (pintype "bidirectional"))
    )
    (net (code "49") (name "Net-(U$24-P$1)") (class "Default")
      (node (ref "U$2") (pin "1") (pinfunction "1_1") (pintype "bidirectional"))
      (node (ref "U$2") (pin "4") (pinfunction "4_4") (pintype "bidirectional"))
      (node (ref "U$24") (pin "C") (pinfunction "P$1_C") (pintype "bidirectional"))
    )
    (net (code "50") (name "Net-(U$25-P$1)") (class "Default")
      (node (ref "U$25") (pin "C") (pinfunction "P$1_C") (pintype "bidirectional"))
      (node (ref "U$3") (pin "1") (pinfunction "1_1") (pintype "bidirectional"))
      (node (ref "U$3") (pin "4") (pinfunction "4_4") (pintype "bidirectional"))
    )
    (net (code "51") (name "Net-(U$26-P$1)") (class "Default")
      (node (ref "U$26") (pin "C") (pinfunction "P$1_C") (pintype "bidirectional"))
      (node (ref "U$4") (pin "1") (pinfunction "1_1") (pintype "bidirectional"))
      (node (ref "U$4") (pin "4") (pinfunction "4_4") (pintype "bidirectional"))
    )
    (net (code "52") (name "Net-(U$27-P$1)") (class "Default")
      (node (ref "U$27") (pin "C") (pinfunction "P$1_C") (pintype "bidirectional"))
      (node (ref "U$5") (pin "1") (pinfunction "1_1") (pintype "bidirectional"))
      (node (ref "U$5") (pin "4") (pinfunction "4_4") (pintype "bidirectional"))
    )
    (net (code "53") (name "Net-(U$28-P$1)") (class "Default")
      (node (ref "U$28") (pin "C") (pinfunction "P$1_C") (pintype "bidirectional"))
      (node (ref "U$6") (pin "1") (pinfunction "1_1") (pintype "bidirectional"))
      (node (ref "U$6") (pin "4") (pinfunction "4_4") (pintype "bidirectional"))
    )
    (net (code "54") (name "Net-(U$29-P$1)") (class "Default")
      (node (ref "U$29") (pin "C") (pinfunction "P$1_C") (pintype "bidirectional"))
      (node (ref "U$7") (pin "1") (pinfunction "1_1") (pintype "bidirectional"))
      (node (ref "U$7") (pin "4") (pinfunction "4_4") (pintype "bidirectional"))
    )
    (net (code "55") (name "Net-(U$30-P$1)") (class "Default")
      (node (ref "U$30") (pin "C") (pinfunction "P$1_C") (pintype "bidirectional"))
      (node (ref "U$8") (pin "1") (pinfunction "1_1") (pintype "bidirectional"))
      (node (ref "U$8") (pin "4") (pinfunction "4_4") (pintype "bidirectional"))
    )
    (net (code "56") (name "Net-(U$31-P$1)") (class "Default")
      (node (ref "U$31") (pin "C") (pinfunction "P$1_C") (pintype "bidirectional"))
      (node (ref "U$9") (pin "1") (pinfunction "1_1") (pintype "bidirectional"))
      (node (ref "U$9") (pin "4") (pinfunction "4_4") (pintype "bidirectional"))
    )
    (net (code "57") (name "Net-(U$32-P$1)") (class "Default")
      (node (ref "U$10") (pin "1") (pinfunction "1_1") (pintype "bidirectional"))
      (node (ref "U$10") (pin "4") (pinfunction "4_4") (pintype "bidirectional"))
      (node (ref "U$32") (pin "C") (pinfunction "P$1_C") (pintype "bidirectional"))
    )
    (net (code "58") (name "Net-(U$33-P$1)") (class "Default")
      (node (ref "U$11") (pin "1") (pinfunction "1_1") (pintype "bidirectional"))
      (node (ref "U$11") (pin "4") (pinfunction "4_4") (pintype "bidirectional"))
      (node (ref "U$33") (pin "C") (pinfunction "P$1_C") (pintype "bidirectional"))
    )
    (net (code "59") (name "Net-(U$34-P$1)") (class "Default")
      (node (ref "U$12") (pin "1") (pinfunction "1_1") (pintype "bidirectional"))
      (node (ref "U$12") (pin "4") (pinfunction "4_4") (pintype "bidirectional"))
      (node (ref "U$34") (pin "C") (pinfunction "P$1_C") (pintype "bidirectional"))
    )
    (net (code "60") (name "Net-(U$35-P$1)") (class "Default")
      (node (ref "U$13") (pin "1") (pinfunction "1_1") (pintype "bidirectional"))
      (node (ref "U$13") (pin "4") (pinfunction "4_4") (pintype "bidirectional"))
      (node (ref "U$35") (pin "C") (pinfunction "P$1_C") (pintype "bidirectional"))
    )
    (net (code "61") (name "Net-(U$36-P$1)") (class "Default")
      (node (ref "U$14") (pin "1") (pinfunction "1_1") (pintype "bidirectional"))
      (node (ref "U$14") (pin "4") (pinfunction "4_4") (pintype "bidirectional"))
      (node (ref "U$36") (pin "C") (pinfunction "P$1_C") (pintype "bidirectional"))
    )
    (net (code "62") (name "Net-(U$37-P$1)") (class "Default")
      (node (ref "U$15") (pin "1") (pinfunction "1_1") (pintype "bidirectional"))
      (node (ref "U$15") (pin "4") (pinfunction "4_4") (pintype "bidirectional"))
      (node (ref "U$37") (pin "C") (pinfunction "P$1_C") (pintype "bidirectional"))
    )
    (net (code "63") (name "Net-(U$38-P$1)") (class "Default")
      (node (ref "U$16") (pin "1") (pinfunction "1_1") (pintype "bidirectional"))
      (node (ref "U$16") (pin "4") (pinfunction "4_4") (pintype "bidirectional"))
      (node (ref "U$38") (pin "C") (pinfunction "P$1_C") (pintype "bidirectional"))
    )
    (net (code "64") (name "Net-(U$39-P$1)") (class "Default")
      (node (ref "U$18") (pin "1") (pinfunction "1_1") (pintype "bidirectional"))
      (node (ref "U$18") (pin "4") (pinfunction "4_4") (pintype "bidirectional"))
      (node (ref "U$39") (pin "C") (pinfunction "P$1_C") (pintype "bidirectional"))
    )
    (net (code "65") (name "Net-(U$40-P$1)") (class "Default")
      (node (ref "U$19") (pin "1") (pinfunction "1_1") (pintype "bidirectional"))
      (node (ref "U$19") (pin "4") (pinfunction "4_4") (pintype "bidirectional"))
      (node (ref "U$40") (pin "C") (pinfunction "P$1_C") (pintype "bidirectional"))
    )
    (net (code "66") (name "Net-(U$41-P$1)") (class "Default")
      (node (ref "U$20") (pin "1") (pinfunction "1_1") (pintype "bidirectional"))
      (node (ref "U$20") (pin "4") (pinfunction "4_4") (pintype "bidirectional"))
      (node (ref "U$41") (pin "C") (pinfunction "P$1_C") (pintype "bidirectional"))
    )
    (net (code "67") (name "Net-(U$42-P$1)") (class "Default")
      (node (ref "U$21") (pin "1") (pinfunction "1_1") (pintype "bidirectional"))
      (node (ref "U$21") (pin "4") (pinfunction "4_4") (pintype "bidirectional"))
      (node (ref "U$42") (pin "C") (pinfunction "P$1_C") (pintype "bidirectional"))
    )
    (net (code "68") (name "Net-(U$43-P$1)") (class "Default")
      (node (ref "U$22") (pin "1") (pinfunction "1_1") (pintype "bidirectional"))
      (node (ref "U$22") (pin "4") (pinfunction "4_4") (pintype "bidirectional"))
      (node (ref "U$43") (pin "C") (pinfunction "P$1_C") (pintype "bidirectional"))
    )
    (net (code "69") (name "Net-(X1-3)") (class "Default")
      (node (ref "MIDI_IN_R") (pin "1") (pinfunction "1_1") (pintype "passive"))
      (node (ref "X1") (pin "R") (pinfunction "3_R") (pintype "bidirectional"))
    )
    (net (code "70") (name "Net-(X1-4)") (class "Default")
      (node (ref "MIDI_IN_T") (pin "1") (pinfunction "1_1") (pintype "passive"))
      (node (ref "X1") (pin "T") (pinfunction "4_T") (pintype "bidirectional"))
    )
    (net (code "71") (name "unconnected-(CLOCK_IN-1-PadP$3)") (class "Default")
      (node (ref "CLOCK_IN") (pin "P$3") (pinfunction "1_P$3") (pintype "passive"))
    )
    (net (code "72") (name "unconnected-(CLOCK_IN-3-PadP$2)") (class "Default")
      (node (ref "CLOCK_IN") (pin "P$2") (pinfunction "3_P$2") (pintype "passive"))
    )
    (net (code "73") (name "unconnected-(CLOCK_OUT-1-PadP$3)") (class "Default")
      (node (ref "CLOCK_OUT") (pin "P$3") (pinfunction "1_P$3") (pintype "passive"))
    )
    (net (code "74") (name "unconnected-(CLOCK_OUT-3-PadP$2)") (class "Default")
      (node (ref "CLOCK_OUT") (pin "P$2") (pinfunction "3_P$2") (pintype "passive"))
    )
    (net (code "75") (name "unconnected-(GATE_IN-1-PadP$3)") (class "Default")
      (node (ref "GATE_IN") (pin "P$3") (pinfunction "1_P$3") (pintype "passive"))
    )
    (net (code "76") (name "unconnected-(GATE_IN-3-PadP$2)") (class "Default")
      (node (ref "GATE_IN") (pin "P$2") (pinfunction "3_P$2") (pintype "passive"))
    )
    (net (code "77") (name "unconnected-(PITCH1_IN-1-PadP$3)") (class "Default")
      (node (ref "PITCH1_IN") (pin "P$3") (pinfunction "1_P$3") (pintype "passive"))
    )
    (net (code "78") (name "unconnected-(PITCH1_IN-3-PadP$2)") (class "Default")
      (node (ref "PITCH1_IN") (pin "P$2") (pinfunction "3_P$2") (pintype "passive"))
    )
    (net (code "79") (name "unconnected-(PITCH2_IN-1-PadP$3)") (class "Default")
      (node (ref "PITCH2_IN") (pin "P$3") (pinfunction "1_P$3") (pintype "passive"))
    )
    (net (code "80") (name "unconnected-(PITCH2_IN-3-PadP$2)") (class "Default")
      (node (ref "PITCH2_IN") (pin "P$2") (pinfunction "3_P$2") (pintype "passive"))
    )
    (net (code "81") (name "unconnected-(PITCH_OUT1-1-PadP$3)") (class "Default")
      (node (ref "PITCH_OUT1") (pin "P$3") (pinfunction "1_P$3") (pintype "passive"))
    )
    (net (code "82") (name "unconnected-(PITCH_OUT1-3-PadP$2)") (class "Default")
      (node (ref "PITCH_OUT1") (pin "P$2") (pinfunction "3_P$2") (pintype "passive"))
    )
    (net (code "83") (name "unconnected-(PITCH_OUT2-1-PadP$3)") (class "Default")
      (node (ref "PITCH_OUT2") (pin "P$3") (pinfunction "1_P$3") (pintype "passive"))
    )
    (net (code "84") (name "unconnected-(PITCH_OUT2-3-PadP$2)") (class "Default")
      (node (ref "PITCH_OUT2") (pin "P$2") (pinfunction "3_P$2") (pintype "passive"))
    )
    (net (code "85") (name "unconnected-(PITCH_OUT3-1-PadP$3)") (class "Default")
      (node (ref "PITCH_OUT3") (pin "P$3") (pinfunction "1_P$3") (pintype "passive"))
    )
    (net (code "86") (name "unconnected-(PITCH_OUT3-3-PadP$2)") (class "Default")
      (node (ref "PITCH_OUT3") (pin "P$2") (pinfunction "3_P$2") (pintype "passive"))
    )
    (net (code "87") (name "unconnected-(PITCH_OUT4-1-PadP$3)") (class "Default")
      (node (ref "PITCH_OUT4") (pin "P$3") (pinfunction "1_P$3") (pintype "passive"))
    )
    (net (code "88") (name "unconnected-(PITCH_OUT4-3-PadP$2)") (class "Default")
      (node (ref "PITCH_OUT4") (pin "P$2") (pinfunction "3_P$2") (pintype "passive"))
    )
    (net (code "89") (name "unconnected-(TRIG_OUT-1-PadP$3)") (class "Default")
      (node (ref "TRIG_OUT") (pin "P$3") (pinfunction "1_P$3") (pintype "passive"))
    )
    (net (code "90") (name "unconnected-(TRIG_OUT-3-PadP$2)") (class "Default")
      (node (ref "TRIG_OUT") (pin "P$2") (pinfunction "3_P$2") (pintype "passive"))
    )
    (net (code "91") (name "unconnected-(X1-2-PadS)") (class "Default")
      (node (ref "X1") (pin "S") (pinfunction "2_S") (pintype "bidirectional"))
    )
  )
)
